# lcd_duffle_smd_mk_3.net
KiCad netlist of a schematic drawn in EAGLE
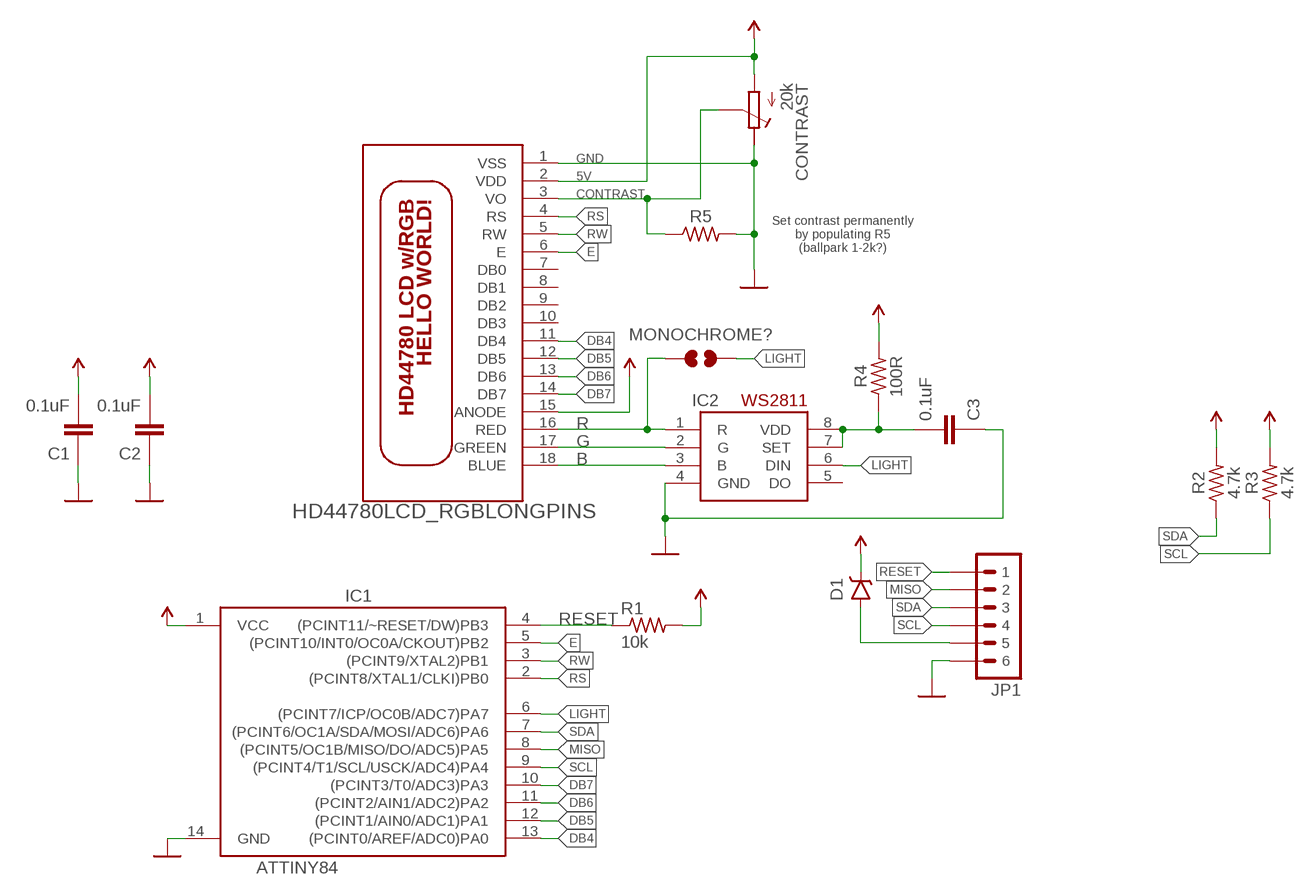
[diagram p0: schematic, sheet 1]

(export (version "E")
  (design (tool "Eeschema 10.0.6"))
  (components
    (comp (ref "C1")
      (value "0.1uF")
      (footprint "eagle-import:C0805")
      (libsource (lib "eagle-import") (part "CAPACITOR-CERAMICC0805"))
    )
    (comp (ref "C2")
      (value "0.1uF")
      (footprint "eagle-import:C0805")
      (libsource (lib "eagle-import") (part "CAPACITOR-CERAMICC0805"))
    )
    (comp (ref "C3")
      (value "0.1uF")
      (footprint "eagle-import:C0805")
      (libsource (lib "eagle-import") (part "CAPACITOR-CERAMICC0805"))
    )
    (comp (ref "CONTRAST")
      (value "20k")
      (footprint "eagle-import:RTRIM3314Z-SIDE")
      (libsource (lib "eagle-import") (part "POTENTIOMETER3314Z"))
    )
    (comp (ref "D1")
      (value "MBRA140")
      (footprint "eagle-import:SMA-DIODE")
      (libsource (lib "eagle-import") (part "DIODE-SCHOTTKYMBRA140"))
    )
    (comp (ref "IC1")
      (value "ATTINY84")
      (footprint "eagle-import:SO14")
      (libsource (lib "eagle-import") (part "ATTINY84"))
    )
    (comp (ref "IC2")
      (value "WS2811")
      (footprint "eagle-import:SO08-SKINNYPADS")
      (libsource (lib "eagle-import") (part "WS2811-SOP8"))
    )
    (comp (ref "JP1")
      (value "M06SMD")
      (footprint "eagle-import:1X06-SMD")
      (libsource (lib "eagle-import") (part "M06SMD"))
    )
    (comp (ref "MONOCHROME?")
      (value "JUMPER-PAD-2-NOYES_SILK")
      (footprint "eagle-import:PAD-JUMPER-2-NO_YES_SILK")
      (libsource (lib "eagle-import") (part "JUMPER-PAD-2-NOYES_SILK"))
    )
    (comp (ref "R1")
      (value "10k")
      (footprint "eagle-import:R0805")
      (libsource (lib "eagle-import") (part "RESISTORR0805"))
    )
    (comp (ref "R2")
      (value "4.7k")
      (footprint "eagle-import:R0805")
      (libsource (lib "eagle-import") (part "RESISTORR0805"))
    )
    (comp (ref "R3")
      (value "4.7k")
      (footprint "eagle-import:R0805")
      (libsource (lib "eagle-import") (part "RESISTORR0805"))
    )
    (comp (ref "R4")
      (value "100R")
      (footprint "eagle-import:R0805")
      (libsource (lib "eagle-import") (part "RESISTORR0805"))
    )
    (comp (ref "R5")
      (value "RESISTORR0805")
      (footprint "eagle-import:R0805")
      (libsource (lib "eagle-import") (part "RESISTORR0805"))
    )
    (comp (ref "U$1")
      (value "HD44780LCD_RGBLONGPINS")
      (footprint "eagle-import:LCD1602-RGB-CENTERED")
      (libsource (lib "eagle-import") (part "HD44780LCD_RGBLONGPINS"))
    )
  )
  (nets
    (net (code "1") (name "/B") (class "Default")
      (node (ref "IC2") (pin "3") (pinfunction "B_3") (pintype "open_collector"))
      (node (ref "U$1") (pin "18") (pinfunction "BLUE_18") (pintype "input"))
    )
    (net (code "2") (name "/CONTRAST") (class "Default")
      (node (ref "CONTRAST") (pin "2") (pinfunction "S_2") (pintype "passive"))
      (node (ref "R5") (pin "1") (pinfunction "1_1") (pintype "passive"))
      (node (ref "U$1") (pin "3") (pinfunction "VO_3") (pintype "input"))
    )
    (net (code "3") (name "/G") (class "Default")
      (node (ref "IC2") (pin "2") (pinfunction "G_2") (pintype "open_collector"))
      (node (ref "U$1") (pin "17") (pinfunction "GREEN_17") (pintype "input"))
    )
    (net (code "4") (name "/R") (class "Default")
      (node (ref "IC2") (pin "1") (pinfunction "R_1") (pintype "open_collector"))
      (node (ref "MONOCHROME?") (pin "1") (pinfunction "1_1") (pintype "passive"))
      (node (ref "U$1") (pin "16") (pinfunction "RED_16") (pintype "input"))
    )
    (net (code "5") (name "5V") (class "Default")
      (node (ref "C1") (pin "2") (pinfunction "2_2") (pintype "passive"))
      (node (ref "C2") (pin "2") (pinfunction "2_2") (pintype "passive"))
      (node (ref "CONTRAST") (pin "1") (pinfunction "A_1") (pintype "passive"))
      (node (ref "D1") (pin "C") (pinfunction "C_C") (pintype "passive"))
      (node (ref "IC1") (pin "1") (pinfunction "VCC_1") (pintype "bidirectional"))
      (node (ref "R1") (pin "2") (pinfunction "2_2") (pintype "passive"))
      (node (ref "R2") (pin "2") (pinfunction "2_2") (pintype "passive"))
      (node (ref "R3") (pin "2") (pinfunction "2_2") (pintype "passive"))
      (node (ref "R4") (pin "2") (pinfunction "2_2") (pintype "passive"))
      (node (ref "U$1") (pin "15") (pinfunction "ANODE_15") (pintype "input"))
      (node (ref "U$1") (pin "2") (pinfunction "VDD_2") (pintype "power_in"))
    )
    (net (code "6") (name "DB4") (class "Default")
      (node (ref "IC1") (pin "13") (pinfunction "(PCINT0/AREF/ADC0)PA0_13") (pintype "bidirectional"))
      (node (ref "U$1") (pin "11") (pinfunction "DB4_11") (pintype "bidirectional"))
    )
    (net (code "7") (name "DB5") (class "Default")
      (node (ref "IC1") (pin "12") (pinfunction "(PCINT1/AIN0/ADC1)PA1_12") (pintype "bidirectional"))
      (node (ref "U$1") (pin "12") (pinfunction "DB5_12") (pintype "bidirectional"))
    )
    (net (code "8") (name "DB6") (class "Default")
      (node (ref "IC1") (pin "11") (pinfunction "(PCINT2/AIN1/ADC2)PA2_11") (pintype "bidirectional"))
      (node (ref "U$1") (pin "13") (pinfunction "DB6_13") (pintype "bidirectional"))
    )
    (net (code "9") (name "DB7") (class "Default")
      (node (ref "IC1") (pin "10") (pinfunction "(PCINT3/T0/ADC3)PA3_10") (pintype "bidirectional"))
      (node (ref "U$1") (pin "14") (pinfunction "DB7_14") (pintype "bidirectional"))
    )
    (net (code "10") (name "E") (class "Default")
      (node (ref "IC1") (pin "5") (pinfunction "(PCINT10/INT0/OC0A/CKOUT)PB2_5") (pintype "bidirectional"))
      (node (ref "U$1") (pin "6") (pinfunction "E_6") (pintype "input"))
    )
    (net (code "11") (name "GND") (class "Default")
      (node (ref "C1") (pin "1") (pinfunction "1_1") (pintype "passive"))
      (node (ref "C2") (pin "1") (pinfunction "1_1") (pintype "passive"))
      (node (ref "C3") (pin "1") (pinfunction "1_1") (pintype "passive"))
      (node (ref "CONTRAST") (pin "3") (pinfunction "E_3") (pintype "passive"))
      (node (ref "IC1") (pin "14") (pinfunction "GND_14") (pintype "bidirectional"))
      (node (ref "IC2") (pin "4") (pinfunction "GND_4") (pintype "power_in"))
      (node (ref "JP1") (pin "6") (pinfunction "6_6") (pintype "passive"))
      (node (ref "R5") (pin "2") (pinfunction "2_2") (pintype "passive"))
      (node (ref "U$1") (pin "1") (pinfunction "VSS_1") (pintype "power_in"))
    )
    (net (code "12") (name "LIGHT") (class "Default")
      (node (ref "IC1") (pin "6") (pinfunction "(PCINT7/ICP/OC0B/ADC7)PA7_6") (pintype "bidirectional"))
      (node (ref "IC2") (pin "6") (pinfunction "DIN_6") (pintype "input"))
      (node (ref "MONOCHROME?") (pin "2") (pinfunction "2_2") (pintype "passive"))
    )
    (net (code "13") (name "MISO") (class "Default")
      (node (ref "IC1") (pin "8") (pinfunction "(PCINT5/OC1B/MISO/DO/ADC5)PA5_8") (pintype "bidirectional"))
      (node (ref "JP1") (pin "2") (pinfunction "2_2") (pintype "passive"))
    )
    (net (code "14") (name "Net-(D1-PadA)") (class "Default")
      (node (ref "D1") (pin "A") (pinfunction "A_A") (pintype "passive"))
      (node (ref "JP1") (pin "5") (pinfunction "5_5") (pintype "passive"))
    )
    (net (code "15") (name "Net-(IC2-SET)") (class "Default")
      (node (ref "C3") (pin "2") (pinfunction "2_2") (pintype "passive"))
      (node (ref "IC2") (pin "7") (pinfunction "SET_7") (pintype "input"))
      (node (ref "IC2") (pin "8") (pinfunction "VDD_8") (pintype "power_in"))
      (node (ref "R4") (pin "1") (pinfunction "1_1") (pintype "passive"))
    )
    (net (code "16") (name "RESET") (class "Default")
      (node (ref "IC1") (pin "4") (pinfunction "(PCINT11/~{RESET/DW})PB3_4") (pintype "bidirectional"))
      (node (ref "JP1") (pin "1") (pinfunction "1_1") (pintype "passive"))
      (node (ref "R1") (pin "1") (pinfunction "1_1") (pintype "passive"))
    )
    (net (code "17") (name "RS") (class "Default")
      (node (ref "IC1") (pin "2") (pinfunction "(PCINT8/XTAL1/CLKI)PB0_2") (pintype "bidirectional"))
      (node (ref "U$1") (pin "4") (pinfunction "RS_4") (pintype "input"))
    )
    (net (code "18") (name "RW") (class "Default")
      (node (ref "IC1") (pin "3") (pinfunction "(PCINT9/XTAL2)PB1_3") (pintype "bidirectional"))
      (node (ref "U$1") (pin "5") (pinfunction "RW_5") (pintype "input"))
    )
    (net (code "19") (name "SCL") (class "Default")
      (node (ref "IC1") (pin "9") (pinfunction "(PCINT4/T1/SCL/USCK/ADC4)PA4_9") (pintype "bidirectional"))
      (node (ref "JP1") (pin "4") (pinfunction "4_4") (pintype "passive"))
      (node (ref "R3") (pin "1") (pinfunction "1_1") (pintype "passive"))
    )
    (net (code "20") (name "SDA") (class "Default")
      (node (ref "IC1") (pin "7") (pinfunction "(PCINT6/OC1A/SDA/MOSI/ADC6)PA6_7") (pintype "bidirectional"))
      (node (ref "JP1") (pin "3") (pinfunction "3_3") (pintype "passive"))
      (node (ref "R2") (pin "1") (pinfunction "1_1") (pintype "passive"))
    )
    (net (code "21") (name "unconnected-(IC2-DO-Pad5)") (class "Default")
      (node (ref "IC2") (pin "5") (pinfunction "DO_5") (pintype "output"))
    )
    (net (code "22") (name "unconnected-(U$1-DB0-Pad7)") (class "Default")
      (node (ref "U$1") (pin "7") (pinfunction "DB0_7") (pintype "bidirectional"))
    )
    (net (code "23") (name "unconnected-(U$1-DB1-Pad8)") (class "Default")
      (node (ref "U$1") (pin "8") (pinfunction "DB1_8") (pintype "bidirectional"))
    )
    (net (code "24") (name "unconnected-(U$1-DB2-Pad9)") (class "Default")
      (node (ref "U$1") (pin "9") (pinfunction "DB2_9") (pintype "bidirectional"))
    )
    (net (code "25") (name "unconnected-(U$1-DB3-Pad10)") (class "Default")
      (node (ref "U$1") (pin "10") (pinfunction "DB3_10") (pintype "bidirectional"))
    )
  )
)
